# EasyEDA_SCHEMATIC.net
KiCad netlist of a schematic drawn in EasyEDA
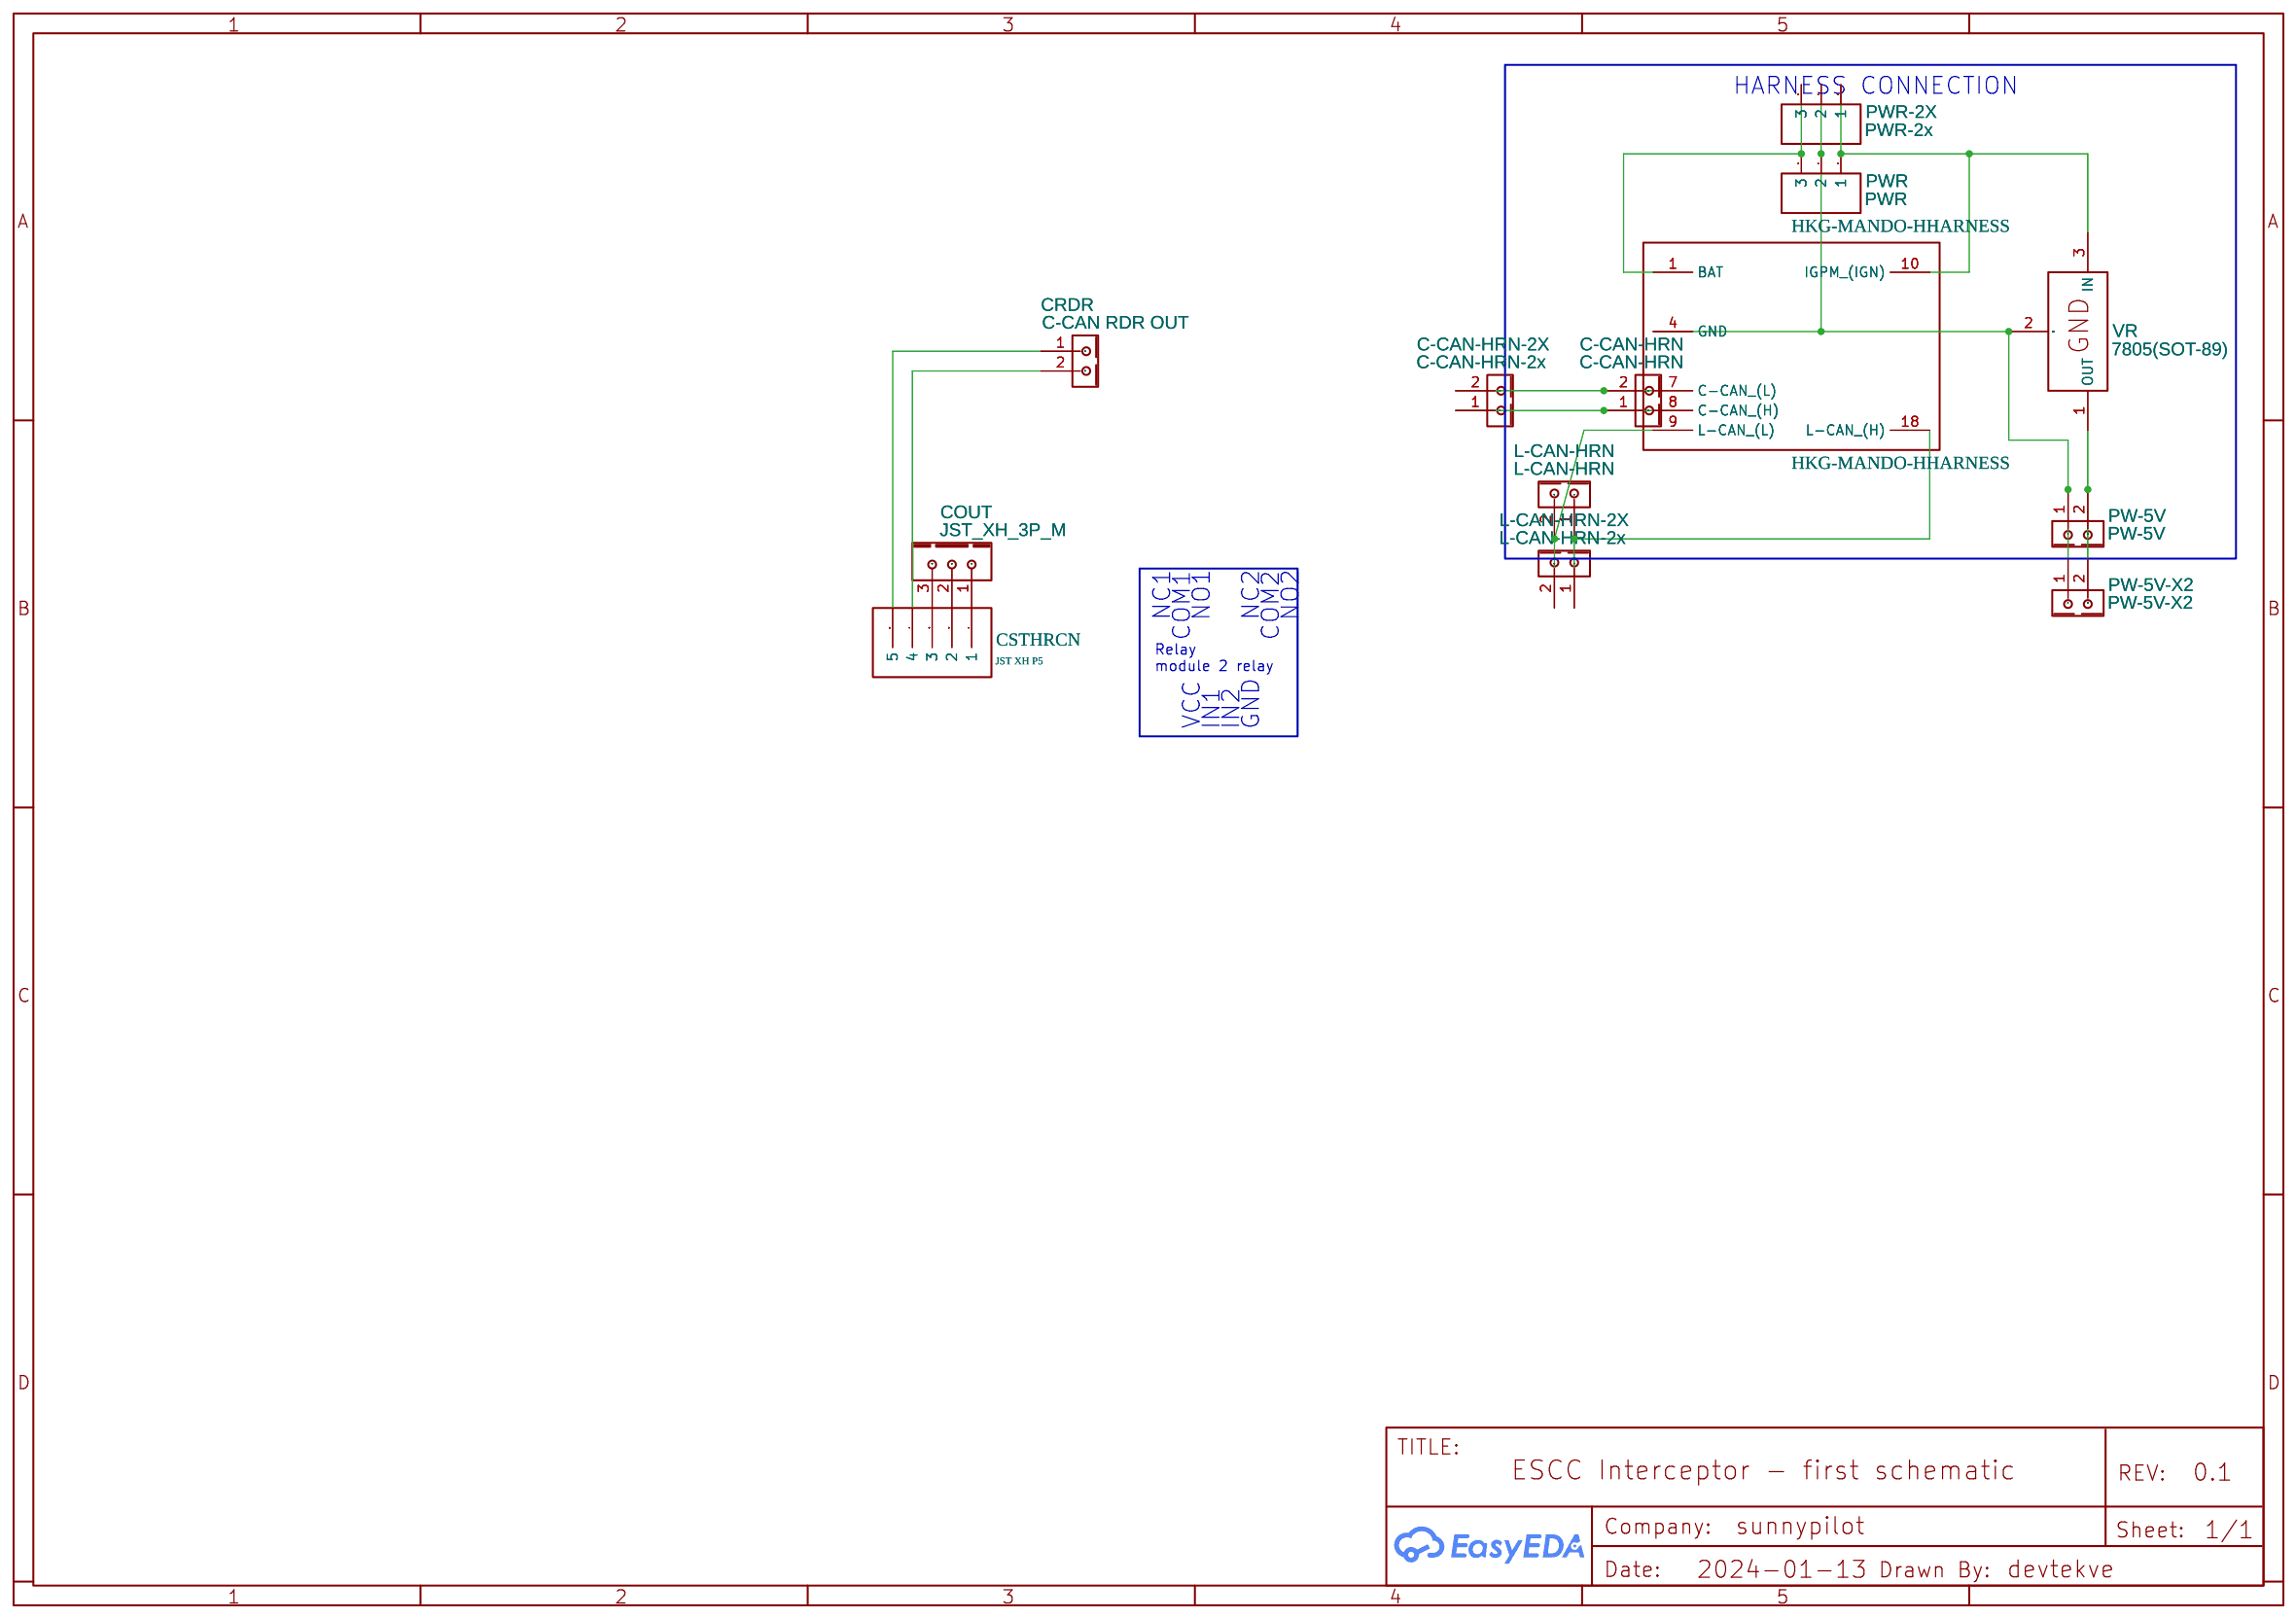
[diagram p0: schematic sheet]

(export (version "E")
  (design (tool "Eeschema 10.0.6"))
  (components
    (comp (ref "C-CAN-HRN") (value "C-CAN-HRN") (libsource (lib "") (part "JST_XH_2P_M_3")))
    (comp (ref "C-CAN-HRN-2X") (value "C-CAN-HRN-2x") (libsource (lib "") (part "JST_XH_2P_M_2")))
    (comp (ref "COUT") (value "JST_XH_3P_M") (libsource (lib "") (part "JST_XH_3P_M")))
    (comp (ref "CRDR") (value "C-CAN RDR OUT") (libsource (lib "") (part "JST_XH_2P_M_4")))
    (comp (ref "CSTHRCN") (value "JST XH P5") (libsource (lib "") (part "Unknown_465_-490")))
    (comp (ref "HKG-MANDO-HHARNESS")
      (value "HKG-MANDO-HHARNESS")
      (libsource (lib "") (part "Unknown_900_-635"))
    )
    (comp (ref "L-CAN-HRN") (value "L-CAN-HRN") (libsource (lib "") (part "JST_XH_2P_M")))
    (comp (ref "L-CAN-HRN-2X") (value "L-CAN-HRN-2x") (libsource (lib "") (part "JST_XH_2P_M_1")))
    (comp (ref "PW-5V") (value "PW-5V") (libsource (lib "") (part "JST_XH_2P_M_5")))
    (comp (ref "PW-5V-X2") (value "PW-5V-X2") (libsource (lib "") (part "JST_XH_2P_M_6")))
    (comp (ref "PWR")
      (value "PWR")
      (fields (field (name "Manufacturer Part") "Header2.54mm 1*3P") (field (name "Manufacturer") "BOOMELE"))
      (libsource (lib "") (part "Unknown_915_-720"))
    )
    (comp (ref "PWR-2X")
      (value "PWR-2x")
      (fields (field (name "Manufacturer Part") "Header2.54mm 1*3P") (field (name "Manufacturer") "BOOMELE"))
      (libsource (lib "") (part "Unknown_915_-755"))
    )
    (comp (ref "VR")
      (value "7805(SOT-89)")
      (fields (field (name "Manufacturer Part") "CJ78L05") (field (name "Manufacturer") "CJ"))
      (libsource (lib "") (part "7805(SOT-89)"))
    )
  )
  (nets
    (net (code "1") (name "Net-(COUT-Pad1)") (class "Default")
      (node (ref "COUT") (pin "1") (pinfunction "1_1") (pintype "unspecified"))
      (node (ref "CSTHRCN") (pin "1") (pinfunction "1_1") (pintype "unspecified"))
    )
    (net (code "2") (name "Net-(COUT-Pad2)") (class "Default")
      (node (ref "COUT") (pin "2") (pinfunction "2_2") (pintype "unspecified"))
      (node (ref "CSTHRCN") (pin "2") (pinfunction "2_2") (pintype "unspecified"))
    )
    (net (code "3") (name "Net-(COUT-Pad3)") (class "Default")
      (node (ref "COUT") (pin "3") (pinfunction "3_3") (pintype "unspecified"))
      (node (ref "CSTHRCN") (pin "3") (pinfunction "3_3") (pintype "unspecified"))
    )
    (net (code "4") (name "Net-(CRDR-Pad1)") (class "Default")
      (node (ref "CRDR") (pin "1") (pinfunction "1_1") (pintype "unspecified"))
      (node (ref "CSTHRCN") (pin "5") (pinfunction "5_5") (pintype "unspecified"))
    )
    (net (code "5") (name "Net-(CRDR-Pad2)") (class "Default")
      (node (ref "CRDR") (pin "2") (pinfunction "2_2") (pintype "unspecified"))
      (node (ref "CSTHRCN") (pin "4") (pinfunction "4_4") (pintype "unspecified"))
    )
    (net (code "6") (name "Net-(HKG-MANDO-HHARNESS-BAT)") (class "Default")
      (node (ref "HKG-MANDO-HHARNESS") (pin "1") (pinfunction "BAT_1") (pintype "passive"))
      (node (ref "PWR") (pin "3") (pinfunction "3_3") (pintype "input"))
      (node (ref "PWR-2X") (pin "3") (pinfunction "3_3") (pintype "input"))
    )
    (net (code "7") (name "Net-(HKG-MANDO-HHARNESS-C-CAN_(H))") (class "Default")
      (node (ref "C-CAN-HRN") (pin "1") (pinfunction "1_1") (pintype "unspecified"))
      (node (ref "C-CAN-HRN-2X") (pin "1") (pinfunction "1_1") (pintype "unspecified"))
      (node (ref "HKG-MANDO-HHARNESS") (pin "8") (pinfunction "C-CAN_(H)_8") (pintype "bidirectional"))
    )
    (net (code "8") (name "Net-(HKG-MANDO-HHARNESS-C-CAN_(L))") (class "Default")
      (node (ref "C-CAN-HRN") (pin "2") (pinfunction "2_2") (pintype "unspecified"))
      (node (ref "C-CAN-HRN-2X") (pin "2") (pinfunction "2_2") (pintype "unspecified"))
      (node (ref "HKG-MANDO-HHARNESS") (pin "7") (pinfunction "C-CAN_(L)_7") (pintype "bidirectional"))
    )
    (net (code "9") (name "Net-(HKG-MANDO-HHARNESS-GND)") (class "Default")
      (node (ref "HKG-MANDO-HHARNESS") (pin "4") (pinfunction "GND_4") (pintype "passive"))
      (node (ref "PW-5V") (pin "1") (pinfunction "1_1") (pintype "unspecified"))
      (node (ref "PW-5V-X2") (pin "1") (pinfunction "1_1") (pintype "unspecified"))
      (node (ref "PWR") (pin "2") (pinfunction "2_2") (pintype "input"))
      (node (ref "PWR-2X") (pin "2") (pinfunction "2_2") (pintype "input"))
      (node (ref "VR") (pin "2") (pinfunction "GND_2") (pintype "passive"))
    )
    (net (code "10") (name "Net-(HKG-MANDO-HHARNESS-IGPM_(IGN))") (class "Default")
      (node (ref "HKG-MANDO-HHARNESS") (pin "10") (pinfunction "IGPM_(IGN)_10") (pintype "passive"))
      (node (ref "PWR") (pin "1") (pinfunction "1_1") (pintype "input"))
      (node (ref "PWR-2X") (pin "1") (pinfunction "1_1") (pintype "input"))
      (node (ref "VR") (pin "3") (pinfunction "IN_3") (pintype "passive"))
    )
    (net (code "11") (name "Net-(HKG-MANDO-HHARNESS-L-CAN_(H))") (class "Default")
      (node (ref "HKG-MANDO-HHARNESS") (pin "18") (pinfunction "L-CAN_(H)_18") (pintype "bidirectional"))
      (node (ref "L-CAN-HRN") (pin "1") (pinfunction "1_1") (pintype "unspecified"))
      (node (ref "L-CAN-HRN-2X") (pin "1") (pinfunction "1_1") (pintype "unspecified"))
    )
    (net (code "12") (name "Net-(HKG-MANDO-HHARNESS-L-CAN_(L))") (class "Default")
      (node (ref "HKG-MANDO-HHARNESS") (pin "9") (pinfunction "L-CAN_(L)_9") (pintype "bidirectional"))
      (node (ref "L-CAN-HRN") (pin "2") (pinfunction "2_2") (pintype "unspecified"))
      (node (ref "L-CAN-HRN-2X") (pin "2") (pinfunction "2_2") (pintype "unspecified"))
    )
    (net (code "13") (name "Net-(VR-OUT)") (class "Default")
      (node (ref "PW-5V") (pin "2") (pinfunction "2_2") (pintype "unspecified"))
      (node (ref "PW-5V-X2") (pin "2") (pinfunction "2_2") (pintype "unspecified"))
      (node (ref "VR") (pin "1") (pinfunction "OUT_1") (pintype "passive"))
    )
  )
)
